# MCU.net
KiCad netlist of a schematic drawn in Altium Designer
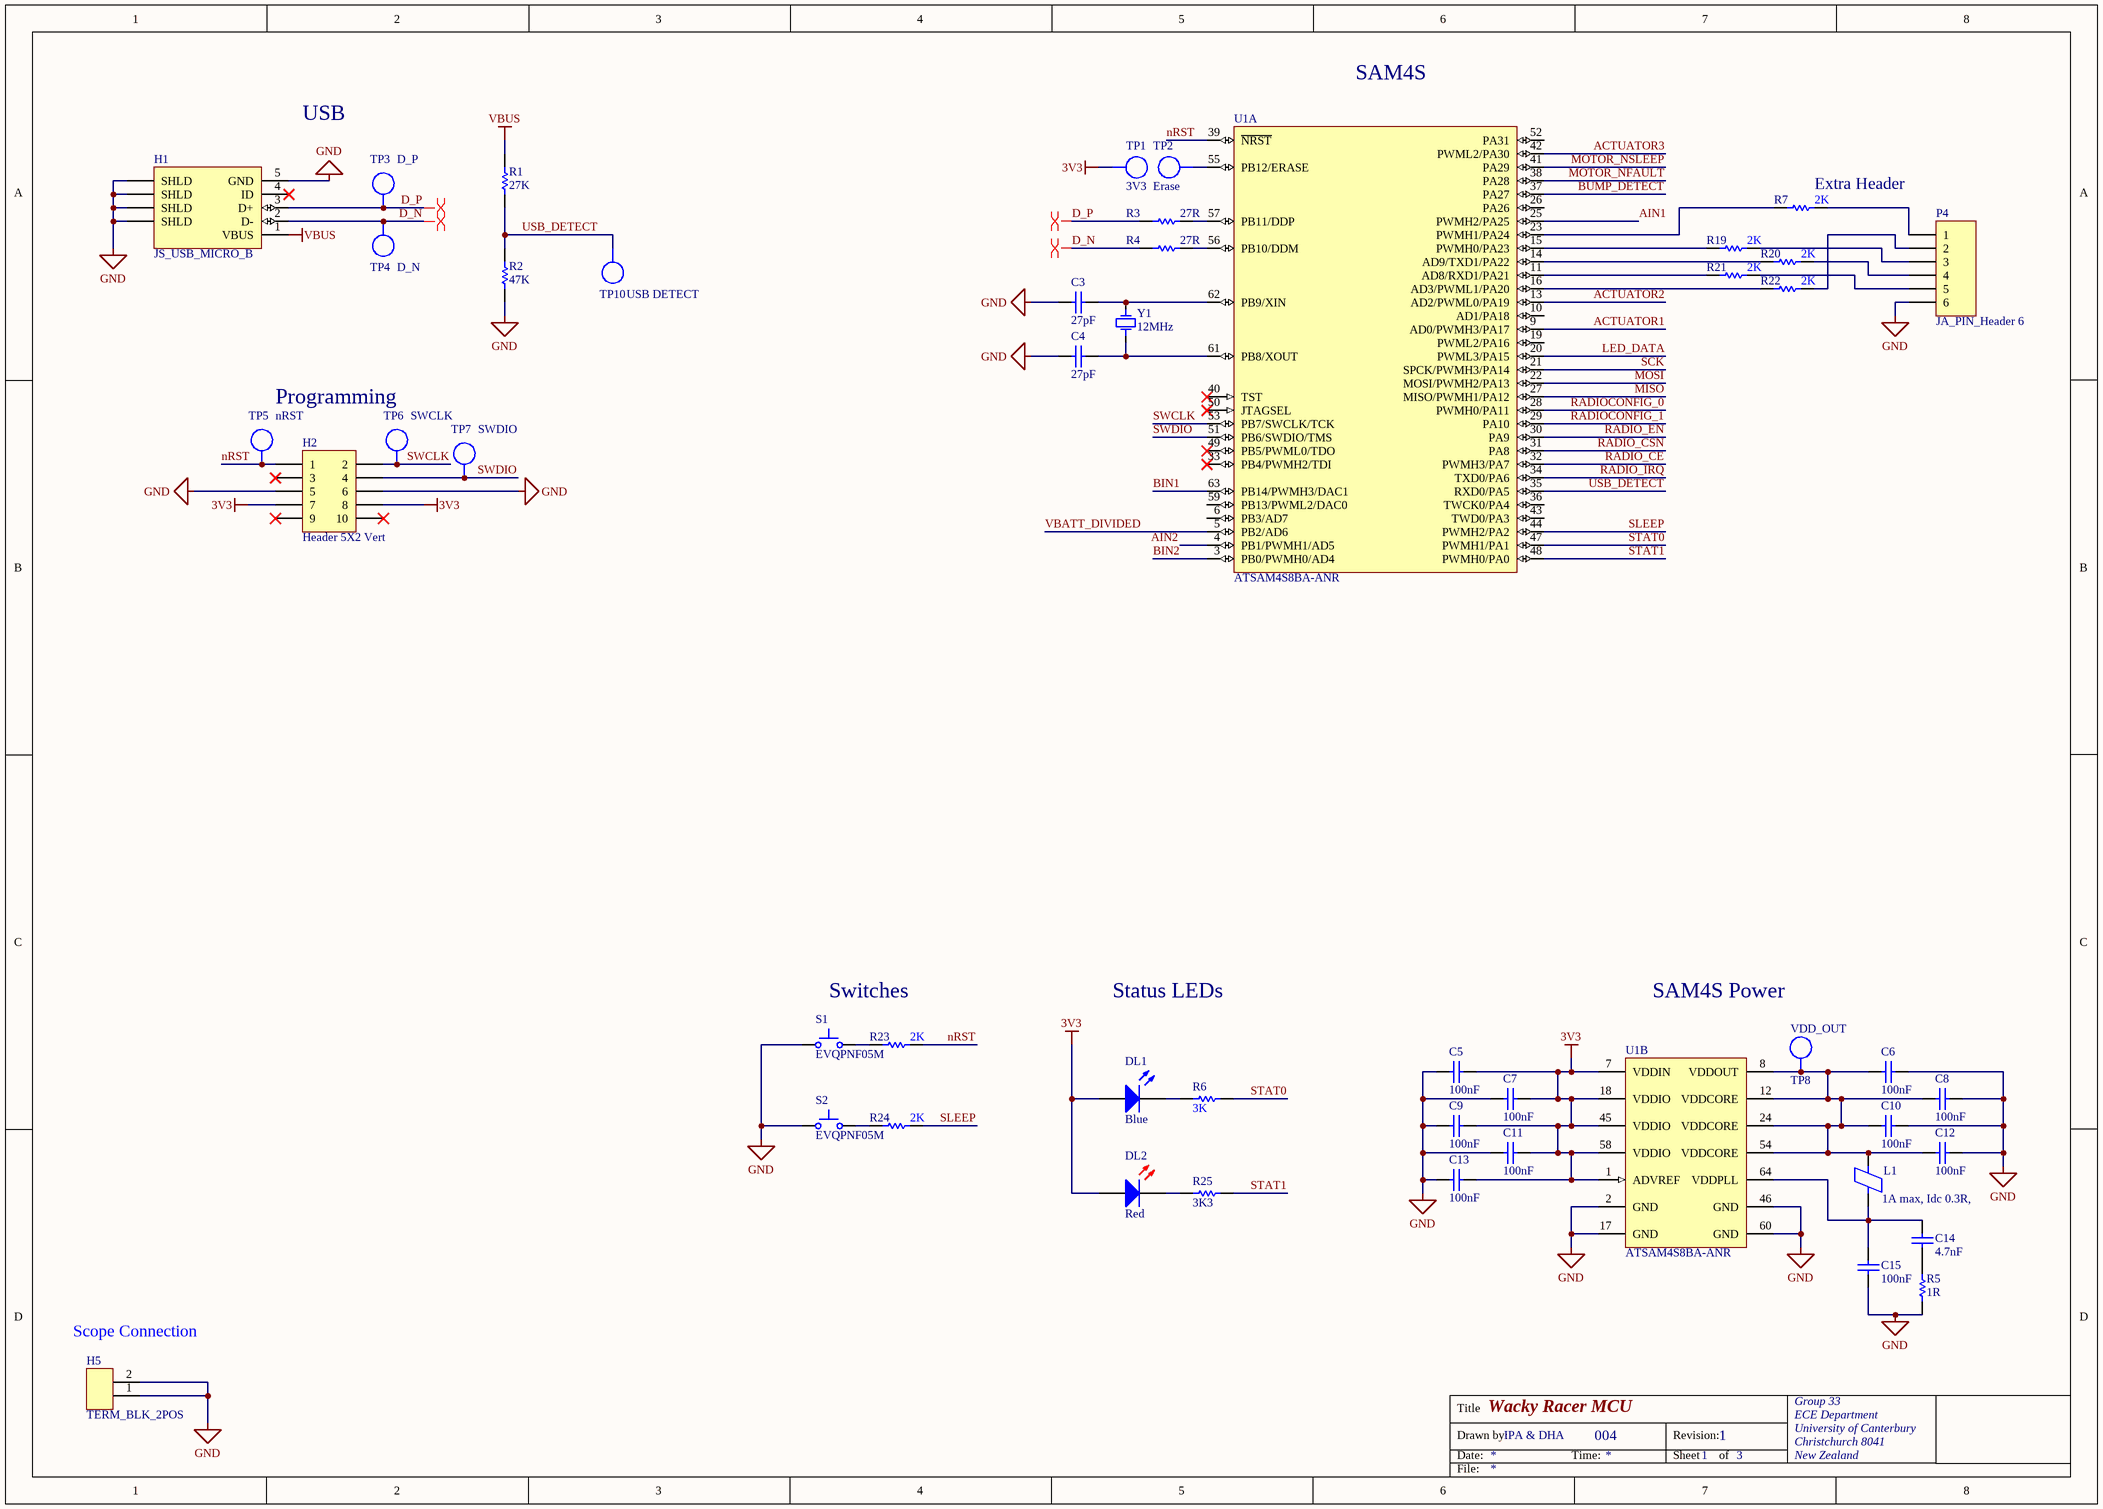
[diagram p0: MCU.SchDoc]

(export (version "E")
  (design (tool "Eeschema 10.0.6"))
  (components
    (comp (ref "C3")
      (value "27pF")
      (footprint "CAPC1608L")
      (description "CAP CER 27pF NPO/COG +-5% 50V 0603")
      (libsource (lib "ECE_ComponentsAD23") (part "CC_27pF_0603"))
    )
    (comp (ref "C4")
      (value "27pF")
      (footprint "CAPC1608L")
      (description "CAP CER 27pF NPO/COG +-5% 50V 0603")
      (libsource (lib "ECE_ComponentsAD23") (part "CC_27pF_0603"))
    )
    (comp (ref "C5")
      (value "100nF")
      (footprint "CAPC1608L")
      (description "CAP CER 100nF X7R +-10% 50V 0603")
      (libsource (lib "ECE_ComponentsAD23") (part "CC_100nF_0603"))
    )
    (comp (ref "C6")
      (value "100nF")
      (footprint "CAPC1608L")
      (description "CAP CER 100nF X7R +-10% 50V 0603")
      (libsource (lib "ECE_ComponentsAD23") (part "CC_100nF_0603"))
    )
    (comp (ref "C7")
      (value "100nF")
      (footprint "CAPC1608L")
      (description "CAP CER 100nF X7R +-10% 50V 0603")
      (libsource (lib "ECE_ComponentsAD23") (part "CC_100nF_0603"))
    )
    (comp (ref "C8")
      (value "100nF")
      (footprint "CAPC1608L")
      (description "CAP CER 100nF X7R +-10% 50V 0603")
      (libsource (lib "ECE_ComponentsAD23") (part "CC_100nF_0603"))
    )
    (comp (ref "C9")
      (value "100nF")
      (footprint "CAPC1608L")
      (description "CAP CER 100nF X7R +-10% 50V 0603")
      (libsource (lib "ECE_ComponentsAD23") (part "CC_100nF_0603"))
    )
    (comp (ref "C10")
      (value "100nF")
      (footprint "CAPC1608L")
      (description "CAP CER 100nF X7R +-10% 50V 0603")
      (libsource (lib "ECE_ComponentsAD23") (part "CC_100nF_0603"))
    )
    (comp (ref "C11")
      (value "100nF")
      (footprint "CAPC1608L")
      (description "CAP CER 100nF X7R +-10% 50V 0603")
      (libsource (lib "ECE_ComponentsAD23") (part "CC_100nF_0603"))
    )
    (comp (ref "C12")
      (value "100nF")
      (footprint "CAPC1608L")
      (description "CAP CER 100nF X7R +-10% 50V 0603")
      (libsource (lib "ECE_ComponentsAD23") (part "CC_100nF_0603"))
    )
    (comp (ref "C13")
      (value "100nF")
      (footprint "CAPC1608L")
      (description "CAP CER 100nF X7R +-10% 50V 0603")
      (libsource (lib "ECE_ComponentsAD23") (part "CC_100nF_0603"))
    )
    (comp (ref "C14")
      (value "4.7nF")
      (footprint "CAPC1608L")
      (description "CAP CER 4.7nF X7R +-10% 50V 0603")
      (libsource (lib "ECE_ComponentsAD23") (part "CC_4.7nF_0603"))
    )
    (comp (ref "C15")
      (value "100nF")
      (footprint "CAPC1608L")
      (description "CAP CER 100nF X7R +-10% 50V 0603")
      (libsource (lib "ECE_ComponentsAD23") (part "CC_100nF_0603"))
    )
    (comp (ref "DL1")
      (value "Blue")
      (footprint "WL-SMCW0603")
      (description "LED Blue 270mcd 0603 SMD")
      (fields
        (field (name "MANUFACTURER") "WURTH ELEKTRONIK")
        (field (name "MANUFACTURER PART NUMBER") "150060BS75000")
        (field (name "LED COLOUR") "Blue")
      )
      (libsource (lib "ECE_ComponentsAD23") (part "DL_150060BS75000"))
    )
    (comp (ref "DL2")
      (value "Red")
      (footprint "WL-SMCW0603")
      (description "LED Red 250mcd 0603 SMD")
      (fields
        (field (name "MANUFACTURER") "WURTH ELEKTRONIK")
        (field (name "MANUFACTURER PART NUMBER") "150060RS75000")
        (field (name "LED COLOUR") "Red")
      )
      (libsource (lib "ECE_ComponentsAD23") (part "DL_150060RS75000"))
    )
    (comp (ref "H1")
      (value "JS_USB_MICRO_B")
      (footprint "FCI_USB_10118194-0001LF")
      (description "CONN USB MICRO B RECPT SMT R/A")
      (fields (field (name "MANUFACTURER") "FCI") (field (name "MANUFACTURER PART NUMBER") "10118194-0001LF"))
      (libsource (lib "ECE_ComponentsAD23") (part "JS_USB_MICRO_B_SMT"))
    )
    (comp (ref "H2")
      (value "Header 5X2 Vert")
      (footprint "IDC2.54-V10D")
      (description "IDC Header, 2,54mm, 10-Pin, Vert")
      (libsource (lib "ECE_ComponentsAD23") (part "JA_HDR_IDC_5X2_VERT"))
    )
    (comp (ref "H5")
      (value "TERM_BLK_2POS")
      (footprint "TERM_BLK_2POS")
      (description "2 Position Terminal Block 7.62mm spacing")
      (libsource (lib "ENCE461AD23") (part "TERM_BLK_2POS"))
    )
    (comp (ref "L1")
      (value "1A max, Idc 0.3R,")
      (footprint "INDC3216L")
      (description "Ferrite Bead, Rdc 0.3R, Z100MHZ 600R, Imax 1A, SMD 1206")
      (fields
        (field (name "MANUFACTURER") "FAIR-RITE")
        (field (name "MANUFACTURER PART NUMBER") "2512066017Y1")
      )
      (libsource (lib "ECE_ComponentsAD23") (part "IN_Ferrite-Bead"))
    )
    (comp (ref "P4")
      (value "JA_PIN_Header 6")
      (footprint "HDR1X6")
      (description "Header, 6-Pin")
      (fields (field (name "PUBLISHER") "Altium Limited"))
      (libsource (lib "ECE_ComponentsAD23") (part "JA_PIN_Header 6"))
    )
    (comp (ref "R1")
      (value "27K")
      (footprint "RESC1608L")
      (description "RES 27K OHM 1/10W 5% 0603 SMD")
      (libsource (lib "ECE_ComponentsAD23") (part "RS_27K"))
    )
    (comp (ref "R2")
      (value "47K")
      (footprint "RESC1608N")
      (description "RES 47.0K OHM 1/10W 5% 0603 SMD")
      (libsource (lib "ECE_ComponentsAD23") (part "RS_47K"))
    )
    (comp (ref "R3")
      (value "27R")
      (footprint "RESC1608L")
      (description "RES 27 OHM 1/10W 5% 0603 SMD")
      (libsource (lib "ECE_ComponentsAD23") (part "RS_27R"))
    )
    (comp (ref "R4")
      (value "27R")
      (footprint "RESC1608L")
      (description "RES 27 OHM 1/10W 5% 0603 SMD")
      (libsource (lib "ECE_ComponentsAD23") (part "RS_27R"))
    )
    (comp (ref "R5")
      (value "1R")
      (footprint "RESC3216L")
      (description "RES 1R OHM 1/4W 5% 1206 SMD")
      (libsource (lib "ECE_ComponentsAD23") (part "RT_1R"))
    )
    (comp (ref "R6")
      (value "3K")
      (footprint "RESC1608L")
      (description "RES 3K OHM 1/10W 5% 0603 SMD")
      (libsource (lib "ECE_ComponentsAD23") (part "RS_3K"))
    )
    (comp (ref "R7")
      (value "2K")
      (footprint "RESC1608L")
      (description "RES 2K OHM 1/10W 5% 0603 SMD")
      (libsource (lib "ECE_ComponentsAD23") (part "RS_2K"))
    )
    (comp (ref "R19")
      (value "2K")
      (footprint "RESC1608L")
      (description "RES 2K OHM 1/10W 5% 0603 SMD")
      (libsource (lib "ECE_ComponentsAD23") (part "RS_2K"))
    )
    (comp (ref "R20")
      (value "2K")
      (footprint "RESC1608L")
      (description "RES 2K OHM 1/10W 5% 0603 SMD")
      (libsource (lib "ECE_ComponentsAD23") (part "RS_2K"))
    )
    (comp (ref "R21")
      (value "2K")
      (footprint "RESC1608L")
      (description "RES 2K OHM 1/10W 5% 0603 SMD")
      (libsource (lib "ECE_ComponentsAD23") (part "RS_2K"))
    )
    (comp (ref "R22")
      (value "2K")
      (footprint "RESC1608L")
      (description "RES 2K OHM 1/10W 5% 0603 SMD")
      (libsource (lib "ECE_ComponentsAD23") (part "RS_2K"))
    )
    (comp (ref "R23")
      (value "2K")
      (footprint "RESC1608L")
      (description "RES 2K OHM 1/10W 5% 0603 SMD")
      (libsource (lib "ECE_ComponentsAD23") (part "RS_2K"))
    )
    (comp (ref "R24")
      (value "2K")
      (footprint "RESC1608L")
      (description "RES 2K OHM 1/10W 5% 0603 SMD")
      (libsource (lib "ECE_ComponentsAD23") (part "RS_2K"))
    )
    (comp (ref "R25")
      (value "3K3")
      (footprint "RESC1608L")
      (description "RES 3.3K OHM 1/10W 5% 0603 SMD")
      (libsource (lib "ECE_ComponentsAD23") (part "RS_3K3"))
    )
    (comp (ref "S1")
      (value "EVQPNF05M")
      (footprint "EVQPNF05M")
      (description "Panasonic 6 x 3.5mm SMD Light Touch Switch Type SMD")
      (fields (field (name "MANUFACTURER") "Panasonic"))
      (libsource (lib "ECE_ComponentsAD23") (part "WS_EVQPNF05M"))
    )
    (comp (ref "S2")
      (value "EVQPNF05M")
      (footprint "EVQPNF05M")
      (description "Panasonic 6 x 3.5mm SMD Light Touch Switch Type SMD")
      (fields (field (name "MANUFACTURER") "Panasonic"))
      (libsource (lib "ECE_ComponentsAD23") (part "WS_EVQPNF05M"))
    )
    (comp (ref "TP1")
      (value "3V3")
      (footprint "TP_1206")
      (description "Test-Point 3.3x1.6x2.1mm SMD")
      (fields
        (field (name "MANUFACTURER") "Harwin Inc")
        (field (name "MANUFACTURER PART NUMBER") "S1751-46R")
      )
      (libsource (lib "ECE_ComponentsAD23") (part "TP_1206"))
    )
    (comp (ref "TP2")
      (value "Erase")
      (footprint "TP_1206")
      (description "Test-Point 3.3x1.6x2.1mm SMD")
      (fields
        (field (name "MANUFACTURER") "Harwin Inc")
        (field (name "MANUFACTURER PART NUMBER") "S1751-46R")
      )
      (libsource (lib "ECE_ComponentsAD23") (part "TP_1206"))
    )
    (comp (ref "TP3")
      (value "D_P")
      (footprint "TP_1206")
      (description "Test-Point 3.3x1.6x2.1mm SMD")
      (fields
        (field (name "MANUFACTURER") "Harwin Inc")
        (field (name "MANUFACTURER PART NUMBER") "S1751-46R")
      )
      (libsource (lib "ECE_ComponentsAD23") (part "TP_1206"))
    )
    (comp (ref "TP4")
      (value "D_N")
      (footprint "TP_1206")
      (description "Test-Point 3.3x1.6x2.1mm SMD")
      (fields
        (field (name "MANUFACTURER") "Harwin Inc")
        (field (name "MANUFACTURER PART NUMBER") "S1751-46R")
      )
      (libsource (lib "ECE_ComponentsAD23") (part "TP_1206"))
    )
    (comp (ref "TP5")
      (value "nRST")
      (footprint "TP_1206")
      (description "Test-Point 3.3x1.6x2.1mm SMD")
      (fields
        (field (name "MANUFACTURER") "Harwin Inc")
        (field (name "MANUFACTURER PART NUMBER") "S1751-46R")
      )
      (libsource (lib "ECE_ComponentsAD23") (part "TP_1206"))
    )
    (comp (ref "TP6")
      (value "SWCLK")
      (footprint "TP_1206")
      (description "Test-Point 3.3x1.6x2.1mm SMD")
      (fields
        (field (name "MANUFACTURER") "Harwin Inc")
        (field (name "MANUFACTURER PART NUMBER") "S1751-46R")
      )
      (libsource (lib "ECE_ComponentsAD23") (part "TP_1206"))
    )
    (comp (ref "TP7")
      (value "SWDIO")
      (footprint "TP_1206")
      (description "Test-Point 3.3x1.6x2.1mm SMD")
      (fields
        (field (name "MANUFACTURER") "Harwin Inc")
        (field (name "MANUFACTURER PART NUMBER") "S1751-46R")
      )
      (libsource (lib "ECE_ComponentsAD23") (part "TP_1206"))
    )
    (comp (ref "TP8")
      (value "VDD_OUT")
      (footprint "TP_1206")
      (description "Test-Point 3.3x1.6x2.1mm SMD")
      (fields
        (field (name "MANUFACTURER") "Harwin Inc")
        (field (name "MANUFACTURER PART NUMBER") "S1751-46R")
      )
      (libsource (lib "ECE_ComponentsAD23") (part "TP_1206"))
    )
    (comp (ref "TP10")
      (value "USB DETECT")
      (footprint "TP_1206")
      (description "Test-Point 3.3x1.6x2.1mm SMD")
      (fields
        (field (name "MANUFACTURER") "Harwin Inc")
        (field (name "MANUFACTURER PART NUMBER") "S1751-46R")
      )
      (libsource (lib "ECE_ComponentsAD23") (part "TP_1206"))
    )
    (comp (ref "U1")
      (value "ATSAM4S8BA-ANR")
      (footprint "LQFP64_L")
      (description "IC MCU 32BIT 512KB FLASH 64LQFP")
      (fields (field (name "MANUFACTURER") "Atmel"))
      (libsource (lib "ECE_ComponentsAD23") (part "SE_ATSAM4S16BA-MU"))
    )
    (comp (ref "Y1")
      (value "12MHz")
      (footprint "6.0X3.5-4")
      (description "CRYSTAL 12MHZ 18PF 6X3.5mm SMD")
      (fields
        (field (name "MANUFACTURER") "CTS-Frequency Controls")
        (field (name "MANUFACTURER PART NUMBER") "406C35D12M00000")
        (field (name "FREQUENCY") "12MHz")
      )
      (libsource (lib "ECE_ComponentsAD23") (part "XT_CRYSTAL_12MHz_18pF"))
    )
  )
  (nets
    (net (code "1") (name "/ACTUATOR1") (class "Default")
      (node (ref "U1") (pin "9") (pinfunction "AD0/PWMH3/PA17_9") (pintype "bidirectional"))
    )
    (net (code "2") (name "/ACTUATOR2") (class "Default")
      (node (ref "U1") (pin "13") (pinfunction "AD2/PWML0/PA19_13") (pintype "bidirectional"))
    )
    (net (code "3") (name "/ACTUATOR3") (class "Default")
      (node (ref "U1") (pin "42") (pinfunction "PWML2/PA30_42") (pintype "bidirectional"))
    )
    (net (code "4") (name "/AIN1") (class "Default")
      (node (ref "U1") (pin "25") (pinfunction "PWMH2/PA25_25") (pintype "bidirectional"))
    )
    (net (code "5") (name "/AIN2") (class "Default")
      (node (ref "U1") (pin "4") (pinfunction "PB1/PWMH1/AD5_4") (pintype "bidirectional"))
    )
    (net (code "6") (name "/BIN1") (class "Default")
      (node (ref "U1") (pin "63") (pinfunction "PB14/PWMH3/DAC1_63") (pintype "bidirectional"))
    )
    (net (code "7") (name "/BIN2") (class "Default")
      (node (ref "U1") (pin "3") (pinfunction "PB0/PWMH0/AD4_3") (pintype "bidirectional"))
    )
    (net (code "8") (name "/BUMP_DETECT") (class "Default")
      (node (ref "U1") (pin "37") (pinfunction "PA27_37") (pintype "bidirectional"))
    )
    (net (code "9") (name "/D_N") (class "Default")
      (node (ref "H1") (pin "2") (pinfunction "D-_2") (pintype "bidirectional"))
      (node (ref "R4") (pin "1") (pinfunction "1_1") (pintype "passive"))
      (node (ref "TP4") (pin "1") (pinfunction "1_1") (pintype "passive"))
    )
    (net (code "10") (name "/D_P") (class "Default")
      (node (ref "H1") (pin "3") (pinfunction "D+_3") (pintype "bidirectional"))
      (node (ref "R3") (pin "1") (pinfunction "1_1") (pintype "passive"))
      (node (ref "TP3") (pin "1") (pinfunction "1_1") (pintype "passive"))
    )
    (net (code "11") (name "/LED_DATA") (class "Default")
      (node (ref "U1") (pin "20") (pinfunction "PWML3/PA15_20") (pintype "bidirectional"))
    )
    (net (code "12") (name "/MISO") (class "Default")
      (node (ref "U1") (pin "27") (pinfunction "MISO/PWMH1/PA12_27") (pintype "bidirectional"))
    )
    (net (code "13") (name "/MOSI") (class "Default")
      (node (ref "U1") (pin "22") (pinfunction "MOSI/PWMH2/PA13_22") (pintype "bidirectional"))
    )
    (net (code "14") (name "/MOTOR_NFAULT") (class "Default")
      (node (ref "U1") (pin "38") (pinfunction "PA28_38") (pintype "bidirectional"))
    )
    (net (code "15") (name "/MOTOR_NSLEEP") (class "Default")
      (node (ref "U1") (pin "41") (pinfunction "PA29_41") (pintype "bidirectional"))
    )
    (net (code "16") (name "/RADIOCONFIG_0") (class "Default")
      (node (ref "U1") (pin "28") (pinfunction "PWMH0/PA11_28") (pintype "bidirectional"))
    )
    (net (code "17") (name "/RADIOCONFIG_1") (class "Default")
      (node (ref "U1") (pin "29") (pinfunction "PA10_29") (pintype "bidirectional"))
    )
    (net (code "18") (name "/RADIO_CE") (class "Default")
      (node (ref "U1") (pin "32") (pinfunction "PWMH3/PA7_32") (pintype "bidirectional"))
    )
    (net (code "19") (name "/RADIO_CSN") (class "Default")
      (node (ref "U1") (pin "31") (pinfunction "PA8_31") (pintype "bidirectional"))
    )
    (net (code "20") (name "/RADIO_EN") (class "Default")
      (node (ref "U1") (pin "30") (pinfunction "PA9_30") (pintype "bidirectional"))
    )
    (net (code "21") (name "/RADIO_IRQ") (class "Default")
      (node (ref "U1") (pin "34") (pinfunction "TXD0/PA6_34") (pintype "bidirectional"))
    )
    (net (code "22") (name "/SCK") (class "Default")
      (node (ref "U1") (pin "21") (pinfunction "SPCK/PWMH3/PA14_21") (pintype "bidirectional"))
    )
    (net (code "23") (name "/SLEEP") (class "Default")
      (node (ref "R24") (pin "2") (pinfunction "2_2") (pintype "passive"))
      (node (ref "U1") (pin "44") (pinfunction "PWMH2/PA2_44") (pintype "bidirectional"))
    )
    (net (code "24") (name "/STAT0") (class "Default")
      (node (ref "R6") (pin "2") (pinfunction "2_2") (pintype "passive"))
      (node (ref "U1") (pin "47") (pinfunction "PWMH1/PA1_47") (pintype "bidirectional"))
    )
    (net (code "25") (name "/STAT1") (class "Default")
      (node (ref "R25") (pin "2") (pinfunction "2_2") (pintype "passive"))
      (node (ref "U1") (pin "48") (pinfunction "PWMH0/PA0_48") (pintype "bidirectional"))
    )
    (net (code "26") (name "/SWCLK") (class "Default")
      (node (ref "H2") (pin "2") (pinfunction "2_2") (pintype "passive"))
      (node (ref "TP6") (pin "1") (pinfunction "1_1") (pintype "passive"))
      (node (ref "U1") (pin "53") (pinfunction "PB7/SWCLK/TCK_53") (pintype "bidirectional"))
    )
    (net (code "27") (name "/SWDIO") (class "Default")
      (node (ref "H2") (pin "4") (pinfunction "4_4") (pintype "passive"))
      (node (ref "TP7") (pin "1") (pinfunction "1_1") (pintype "passive"))
      (node (ref "U1") (pin "51") (pinfunction "PB6/SWDIO/TMS_51") (pintype "bidirectional"))
    )
    (net (code "28") (name "/USB_DETECT") (class "Default")
      (node (ref "R1") (pin "1") (pinfunction "1_1") (pintype "passive"))
      (node (ref "R2") (pin "2") (pinfunction "2_2") (pintype "passive"))
      (node (ref "TP10") (pin "1") (pinfunction "1_1") (pintype "passive"))
      (node (ref "U1") (pin "35") (pinfunction "RXD0/PA5_35") (pintype "bidirectional"))
    )
    (net (code "29") (name "/VBATT_DIVIDED") (class "Default")
      (node (ref "U1") (pin "5") (pinfunction "PB2/AD6_5") (pintype "bidirectional"))
    )
    (net (code "30") (name "/nRST") (class "Default")
      (node (ref "H2") (pin "1") (pinfunction "1_1") (pintype "passive"))
      (node (ref "R23") (pin "2") (pinfunction "2_2") (pintype "passive"))
      (node (ref "TP5") (pin "1") (pinfunction "1_1") (pintype "passive"))
      (node (ref "U1") (pin "39") (pinfunction "~{NRST}_39") (pintype "bidirectional"))
    )
    (net (code "31") (name "3V3") (class "Default")
      (node (ref "C11") (pin "2") (pinfunction "2_2") (pintype "passive"))
      (node (ref "C13") (pin "2") (pinfunction "2_2") (pintype "passive"))
      (node (ref "C5") (pin "2") (pinfunction "2_2") (pintype "passive"))
      (node (ref "C7") (pin "2") (pinfunction "2_2") (pintype "passive"))
      (node (ref "C9") (pin "2") (pinfunction "2_2") (pintype "passive"))
      (node (ref "DL1") (pin "2") (pinfunction "A_2") (pintype "passive"))
      (node (ref "DL2") (pin "2") (pinfunction "A_2") (pintype "passive"))
      (node (ref "H2") (pin "7") (pinfunction "7_7") (pintype "passive"))
      (node (ref "H2") (pin "8") (pinfunction "8_8") (pintype "passive"))
      (node (ref "TP1") (pin "1") (pinfunction "1_1") (pintype "passive"))
      (node (ref "U1") (pin "1") (pinfunction "ADVREF_1") (pintype "input"))
      (node (ref "U1") (pin "18") (pinfunction "VDDIO_18") (pintype "power_in"))
      (node (ref "U1") (pin "45") (pinfunction "VDDIO_45") (pintype "power_in"))
      (node (ref "U1") (pin "58") (pinfunction "VDDIO_58") (pintype "power_in"))
      (node (ref "U1") (pin "7") (pinfunction "VDDIN_7") (pintype "power_in"))
    )
    (net (code "32") (name "GND") (class "Default")
      (node (ref "C10") (pin "2") (pinfunction "2_2") (pintype "passive"))
      (node (ref "C11") (pin "1") (pinfunction "1_1") (pintype "passive"))
      (node (ref "C12") (pin "2") (pinfunction "2_2") (pintype "passive"))
      (node (ref "C13") (pin "1") (pinfunction "1_1") (pintype "passive"))
      (node (ref "C15") (pin "1") (pinfunction "1_1") (pintype "passive"))
      (node (ref "C3") (pin "1") (pinfunction "1_1") (pintype "passive"))
      (node (ref "C4") (pin "1") (pinfunction "1_1") (pintype "passive"))
      (node (ref "C5") (pin "1") (pinfunction "1_1") (pintype "passive"))
      (node (ref "C6") (pin "2") (pinfunction "2_2") (pintype "passive"))
      (node (ref "C7") (pin "1") (pinfunction "1_1") (pintype "passive"))
      (node (ref "C8") (pin "2") (pinfunction "2_2") (pintype "passive"))
      (node (ref "C9") (pin "1") (pinfunction "1_1") (pintype "passive"))
      (node (ref "H1") (pin "5") (pinfunction "GND_5") (pintype "passive"))
      (node (ref "H1") (pin "6") (pinfunction "SHLD_6") (pintype "passive"))
      (node (ref "H2") (pin "5") (pinfunction "5_5") (pintype "passive"))
      (node (ref "H2") (pin "6") (pinfunction "6_6") (pintype "passive"))
      (node (ref "H5") (pin "1") (pintype "passive"))
      (node (ref "H5") (pin "2") (pintype "passive"))
      (node (ref "P4") (pin "6") (pinfunction "6_6") (pintype "passive"))
      (node (ref "R2") (pin "1") (pinfunction "1_1") (pintype "passive"))
      (node (ref "R5") (pin "1") (pinfunction "1_1") (pintype "passive"))
      (node (ref "S1") (pin "1") (pintype "passive"))
      (node (ref "S2") (pin "1") (pintype "passive"))
      (node (ref "U1") (pin "17") (pinfunction "GND_17") (pintype "power_in"))
      (node (ref "U1") (pin "2") (pinfunction "GND_2") (pintype "power_in"))
      (node (ref "U1") (pin "46") (pinfunction "GND_46") (pintype "power_in"))
      (node (ref "U1") (pin "60") (pinfunction "GND_60") (pintype "power_in"))
    )
    (net (code "33") (name "Net-(C14-Pad1)") (class "Default")
      (node (ref "C14") (pin "1") (pinfunction "1_1") (pintype "passive"))
      (node (ref "R5") (pin "2") (pinfunction "2_2") (pintype "passive"))
    )
    (net (code "34") (name "Net-(DL1-K)") (class "Default")
      (node (ref "DL1") (pin "1") (pinfunction "K_1") (pintype "passive"))
      (node (ref "R6") (pin "1") (pinfunction "1_1") (pintype "passive"))
    )
    (net (code "35") (name "Net-(DL2-K)") (class "Default")
      (node (ref "DL2") (pin "1") (pinfunction "K_1") (pintype "passive"))
      (node (ref "R25") (pin "1") (pinfunction "1_1") (pintype "passive"))
    )
    (net (code "36") (name "Net-(P4-Pad1)") (class "Default")
      (node (ref "P4") (pin "1") (pinfunction "1_1") (pintype "passive"))
      (node (ref "R7") (pin "2") (pinfunction "2_2") (pintype "passive"))
    )
    (net (code "37") (name "Net-(P4-Pad2)") (class "Default")
      (node (ref "P4") (pin "2") (pinfunction "2_2") (pintype "passive"))
      (node (ref "R22") (pin "2") (pinfunction "2_2") (pintype "passive"))
    )
    (net (code "38") (name "Net-(P4-Pad3)") (class "Default")
      (node (ref "P4") (pin "3") (pinfunction "3_3") (pintype "passive"))
      (node (ref "R19") (pin "2") (pinfunction "2_2") (pintype "passive"))
    )
    (net (code "39") (name "Net-(P4-Pad4)") (class "Default")
      (node (ref "P4") (pin "4") (pinfunction "4_4") (pintype "passive"))
      (node (ref "R20") (pin "2") (pinfunction "2_2") (pintype "passive"))
    )
    (net (code "40") (name "Net-(P4-Pad5)") (class "Default")
      (node (ref "P4") (pin "5") (pinfunction "5_5") (pintype "passive"))
      (node (ref "R21") (pin "2") (pinfunction "2_2") (pintype "passive"))
    )
    (net (code "41") (name "Net-(R23-Pad1)") (class "Default")
      (node (ref "R23") (pin "1") (pinfunction "1_1") (pintype "passive"))
      (node (ref "S1") (pin "2") (pintype "passive"))
    )
    (net (code "42") (name "Net-(R24-Pad1)") (class "Default")
      (node (ref "R24") (pin "1") (pinfunction "1_1") (pintype "passive"))
      (node (ref "S2") (pin "2") (pintype "passive"))
    )
    (net (code "43") (name "Net-(U1A-AD3{slash}PWML1{slash}PA20)") (class "Default")
      (node (ref "R22") (pin "1") (pinfunction "1_1") (pintype "passive"))
      (node (ref "U1") (pin "16") (pinfunction "AD3/PWML1/PA20_16") (pintype "bidirectional"))
    )
    (net (code "44") (name "Net-(U1A-AD8{slash}RXD1{slash}PA21)") (class "Default")
      (node (ref "R21") (pin "1") (pinfunction "1_1") (pintype "passive"))
      (node (ref "U1") (pin "11") (pinfunction "AD8/RXD1/PA21_11") (pintype "bidirectional"))
    )
    (net (code "45") (name "Net-(U1A-AD9{slash}TXD1{slash}PA22)") (class "Default")
      (node (ref "R20") (pin "1") (pinfunction "1_1") (pintype "passive"))
      (node (ref "U1") (pin "14") (pinfunction "AD9/TXD1/PA22_14") (pintype "bidirectional"))
    )
    (net (code "46") (name "Net-(U1A-PB8{slash}XOUT)") (class "Default")
      (node (ref "C4") (pin "2") (pinfunction "2_2") (pintype "passive"))
      (node (ref "U1") (pin "61") (pinfunction "PB8/XOUT_61") (pintype "bidirectional"))
      (node (ref "Y1") (pin "1") (pinfunction "OSC1_1") (pintype "passive"))
    )
    (net (code "47") (name "Net-(U1A-PB9{slash}XIN)") (class "Default")
      (node (ref "C3") (pin "2") (pinfunction "2_2") (pintype "passive"))
      (node (ref "U1") (pin "62") (pinfunction "PB9/XIN_62") (pintype "bidirectional"))
      (node (ref "Y1") (pin "3") (pinfunction "OSC2_3") (pintype "passive"))
    )
    (net (code "48") (name "Net-(U1A-PB10{slash}DDM)") (class "Default")
      (node (ref "R4") (pin "2") (pinfunction "2_2") (pintype "passive"))
      (node (ref "U1") (pin "56") (pinfunction "PB10/DDM_56") (pintype "bidirectional"))
    )
    (net (code "49") (name "Net-(U1A-PB11{slash}DDP)") (class "Default")
      (node (ref "R3") (pin "2") (pinfunction "2_2") (pintype "passive"))
      (node (ref "U1") (pin "57") (pinfunction "PB11/DDP_57") (pintype "bidirectional"))
    )
    (net (code "50") (name "Net-(U1A-PB12{slash}ERASE)") (class "Default")
      (node (ref "TP2") (pin "1") (pinfunction "1_1") (pintype "passive"))
      (node (ref "U1") (pin "55") (pinfunction "PB12/ERASE_55") (pintype "bidirectional"))
    )
    (net (code "51") (name "Net-(U1A-PWMH0{slash}PA23)") (class "Default")
      (node (ref "R19") (pin "1") (pinfunction "1_1") (pintype "passive"))
      (node (ref "U1") (pin "15") (pinfunction "PWMH0/PA23_15") (pintype "bidirectional"))
    )
    (net (code "52") (name "Net-(U1A-PWMH1{slash}PA24)") (class "Default")
      (node (ref "R7") (pin "1") (pinfunction "1_1") (pintype "passive"))
      (node (ref "U1") (pin "23") (pinfunction "PWMH1/PA24_23") (pintype "bidirectional"))
    )
    (net (code "53") (name "Net-(U1B-VDDOUT)") (class "Default")
      (node (ref "C10") (pin "1") (pinfunction "1_1") (pintype "passive"))
      (node (ref "C12") (pin "1") (pinfunction "1_1") (pintype "passive"))
      (node (ref "C6") (pin "1") (pinfunction "1_1") (pintype "passive"))
      (node (ref "C8") (pin "1") (pinfunction "1_1") (pintype "passive"))
      (node (ref "L1") (pin "2") (pinfunction "2_2") (pintype "passive"))
      (node (ref "TP8") (pin "1") (pinfunction "1_1") (pintype "passive"))
      (node (ref "U1") (pin "12") (pinfunction "VDDCORE_12") (pintype "power_in"))
      (node (ref "U1") (pin "24") (pinfunction "VDDCORE_24") (pintype "power_in"))
      (node (ref "U1") (pin "54") (pinfunction "VDDCORE_54") (pintype "power_in"))
      (node (ref "U1") (pin "8") (pinfunction "VDDOUT_8") (pintype "power_in"))
    )
    (net (code "54") (name "Net-(U1B-VDDPLL)") (class "Default")
      (node (ref "C14") (pin "2") (pinfunction "2_2") (pintype "passive"))
      (node (ref "C15") (pin "2") (pinfunction "2_2") (pintype "passive"))
      (node (ref "L1") (pin "1") (pinfunction "1_1") (pintype "passive"))
      (node (ref "U1") (pin "64") (pinfunction "VDDPLL_64") (pintype "power_in"))
    )
    (net (code "55") (name "VBUS") (class "Default")
      (node (ref "H1") (pin "1") (pinfunction "VBUS_1") (pintype "power_in"))
      (node (ref "R1") (pin "2") (pinfunction "2_2") (pintype "passive"))
    )
    (net (code "56") (name "unconnected-(H1-ID-Pad4)") (class "Default")
      (node (ref "H1") (pin "4") (pinfunction "ID_4") (pintype "power_in+no_connect"))
    )
    (net (code "57") (name "unconnected-(H2-Pad3)") (class "Default")
      (node (ref "H2") (pin "3") (pinfunction "3_3") (pintype "passive+no_connect"))
    )
    (net (code "58") (name "unconnected-(H2-Pad9)") (class "Default")
      (node (ref "H2") (pin "9") (pinfunction "9_9") (pintype "passive+no_connect"))
    )
    (net (code "59") (name "unconnected-(H2-Pad10)") (class "Default")
      (node (ref "H2") (pin "10") (pinfunction "10_10") (pintype "passive+no_connect"))
    )
    (net (code "60") (name "unconnected-(U1A-AD1{slash}PA18-Pad10)") (class "Default")
      (node (ref "U1") (pin "10") (pinfunction "AD1/PA18_10") (pintype "bidirectional"))
    )
    (net (code "61") (name "unconnected-(U1A-JTAGSEL-Pad50)") (class "Default")
      (node (ref "U1") (pin "50") (pinfunction "JTAGSEL_50") (pintype "input+no_connect"))
    )
    (net (code "62") (name "unconnected-(U1A-PA26-Pad26)") (class "Default")
      (node (ref "U1") (pin "26") (pinfunction "PA26_26") (pintype "bidirectional"))
    )
    (net (code "63") (name "unconnected-(U1A-PA31-Pad52)") (class "Default")
      (node (ref "U1") (pin "52") (pinfunction "PA31_52") (pintype "bidirectional"))
    )
    (net (code "64") (name "unconnected-(U1A-PB3{slash}AD7-Pad6)") (class "Default")
      (node (ref "U1") (pin "6") (pinfunction "PB3/AD7_6") (pintype "bidirectional"))
    )
    (net (code "65") (name "unconnected-(U1A-PB4{slash}PWMH2{slash}TDI-Pad33)") (class "Default")
      (node (ref "U1") (pin "33") (pinfunction "PB4/PWMH2/TDI_33") (pintype "bidirectional+no_connect"))
    )
    (net (code "66") (name "unconnected-(U1A-PB5{slash}PWML0{slash}TDO-Pad49)") (class "Default")
      (node (ref "U1") (pin "49") (pinfunction "PB5/PWML0/TDO_49") (pintype "bidirectional+no_connect"))
    )
    (net (code "67") (name "unconnected-(U1A-PB13{slash}PWML2{slash}DAC0-Pad59)") (class "Default")
      (node (ref "U1") (pin "59") (pinfunction "PB13/PWML2/DAC0_59") (pintype "bidirectional"))
    )
    (net (code "68") (name "unconnected-(U1A-PWML2{slash}PA16-Pad19)") (class "Default")
      (node (ref "U1") (pin "19") (pinfunction "PWML2/PA16_19") (pintype "bidirectional"))
    )
    (net (code "69") (name "unconnected-(U1A-TST-Pad40)") (class "Default")
      (node (ref "U1") (pin "40") (pinfunction "TST_40") (pintype "input+no_connect"))
    )
    (net (code "70") (name "unconnected-(U1A-TWCK0{slash}PA4-Pad36)") (class "Default")
      (node (ref "U1") (pin "36") (pinfunction "TWCK0/PA4_36") (pintype "bidirectional"))
    )
    (net (code "71") (name "unconnected-(U1A-TWD0{slash}PA3-Pad43)") (class "Default")
      (node (ref "U1") (pin "43") (pinfunction "TWD0/PA3_43") (pintype "bidirectional"))
    )
  )
)
